# POWER.net
KiCad netlist of a schematic drawn in Altium Designer
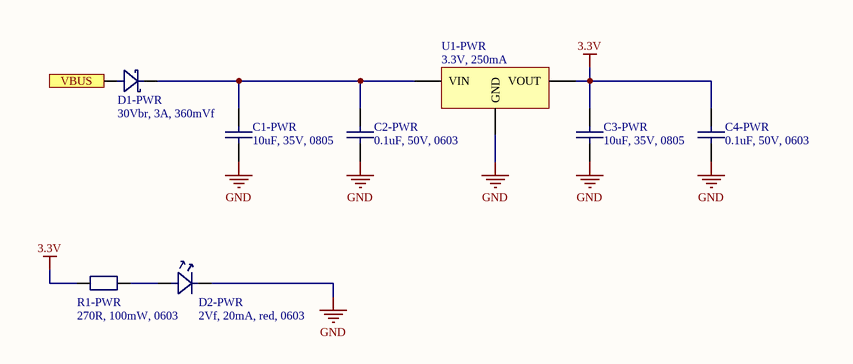
[diagram p0: POWER.SchDoc]

(export (version "E")
  (design (tool "Eeschema 10.0.6"))
  (components
    (comp (ref "C1-PWR")
      (value "10uF, 35V, 0805")
      (footprint "0805 [2012]")
      (fields (field (name "MANUFACTURER") "MURATA"))
      (libsource (lib "SCH-LIB") (part "Capacitor"))
    )
    (comp (ref "C2-PWR")
      (value "0.1uF, 50V, 0603")
      (footprint "0603 [1608]")
      (fields (field (name "MANUFACTURER") "MULTICOMP PRO"))
      (libsource (lib "SCH-LIB") (part "Capacitor"))
    )
    (comp (ref "C3-PWR")
      (value "10uF, 35V, 0805")
      (footprint "0805 [2012]")
      (fields (field (name "MANUFACTURER") "MURATA"))
      (libsource (lib "SCH-LIB") (part "Capacitor"))
    )
    (comp (ref "C4-PWR")
      (value "0.1uF, 50V, 0603")
      (footprint "0603 [1608]")
      (fields (field (name "MANUFACTURER") "MULTICOMP PRO"))
      (libsource (lib "SCH-LIB") (part "Capacitor"))
    )
    (comp (ref "D1-PWR")
      (value "30Vbr, 3A, 360mVf")
      (footprint "SOD-128")
      (fields (field (name "MANUFACTURER") "NEXPERIA"))
      (libsource (lib "SCH-LIB") (part "Schottky Rectifier (Diode)"))
    )
    (comp (ref "D2-PWR")
      (value "2Vf, 20mA, red, 0603")
      (footprint "LED 0603 [1608]")
      (fields (field (name "MANUFACTURER") "VISHAY"))
      (libsource (lib "SCH-LIB") (part "LED"))
    )
    (comp (ref "R1-PWR")
      (value "270R, 100mW, 0603")
      (footprint "0603 [1608]")
      (fields (field (name "MANUFACTURER") "YAGEO"))
      (libsource (lib "SCH-LIB") (part "Resistor"))
    )
    (comp (ref "U1-PWR")
      (value "3.3V, 250mA")
      (footprint "SOT-23-3")
      (description "Fixed LDO Voltage Regulator, 2.3V to 6V, 178mV Dropout, 3.3Vout, 250mAout, SOT-23-3")
      (fields (field (name "MANUFACTURER") "Microchip"))
      (libsource (lib "SCH-LIB") (part "LDO Regulator"))
    )
  )
  (nets
    (net (code "1") (name "/VBUS") (class "Default")
      (node (ref "D1-PWR") (pin "2") (pinfunction "2_2") (pintype "passive"))
    )
    (net (code "2") (name "3.3V") (class "Default")
      (node (ref "C3-PWR") (pin "1") (pinfunction "1_1") (pintype "passive"))
      (node (ref "C4-PWR") (pin "2") (pinfunction "2_2") (pintype "passive"))
      (node (ref "R1-PWR") (pin "2") (pinfunction "2_2") (pintype "passive"))
      (node (ref "U1-PWR") (pin "2") (pinfunction "VOUT_2") (pintype "passive"))
    )
    (net (code "3") (name "GND") (class "Default")
      (node (ref "C1-PWR") (pin "2") (pinfunction "2_2") (pintype "passive"))
      (node (ref "C2-PWR") (pin "1") (pinfunction "1_1") (pintype "passive"))
      (node (ref "C3-PWR") (pin "2") (pinfunction "2_2") (pintype "passive"))
      (node (ref "C4-PWR") (pin "1") (pinfunction "1_1") (pintype "passive"))
      (node (ref "D2-PWR") (pin "1") (pinfunction "1_1") (pintype "passive"))
      (node (ref "U1-PWR") (pin "1") (pinfunction "GND_1") (pintype "passive"))
    )
    (net (code "4") (name "Net-(D2-PWR-Pad2)") (class "Default")
      (node (ref "D2-PWR") (pin "2") (pinfunction "2_2") (pintype "passive"))
      (node (ref "R1-PWR") (pin "1") (pinfunction "1_1") (pintype "passive"))
    )
    (net (code "5") (name "Net-(U1-PWR-VIN)") (class "Default")
      (node (ref "C1-PWR") (pin "1") (pinfunction "1_1") (pintype "passive"))
      (node (ref "C2-PWR") (pin "2") (pinfunction "2_2") (pintype "passive"))
      (node (ref "D1-PWR") (pin "1") (pinfunction "1_1") (pintype "passive"))
      (node (ref "U1-PWR") (pin "3") (pinfunction "VIN_3") (pintype "passive"))
    )
  )
)
